# RS_485.net
KiCad netlist of a schematic drawn in Altium Designer
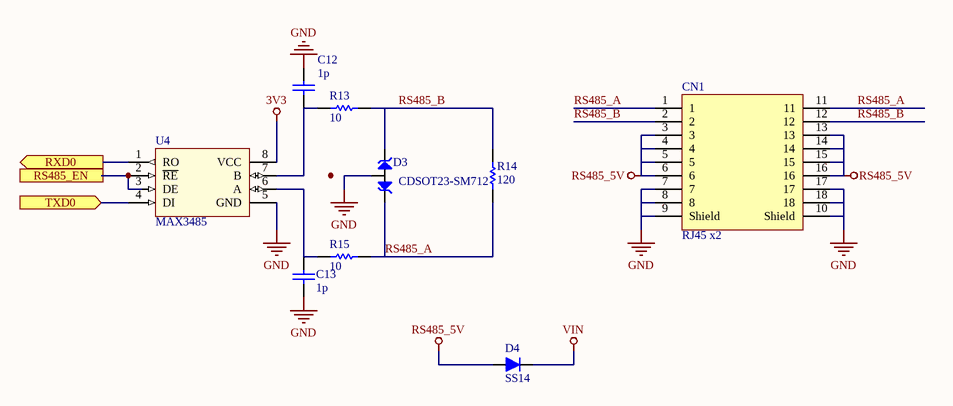
[diagram p0: RS_485.SchDoc]

(export (version "E")
  (design (tool "Eeschema 10.0.6"))
  (components
    (comp (ref "C12")
      (value "1p")
      (description "Capacitor")
      (libsource (lib "Simulation Generic Components") (part "Capacitor"))
    )
    (comp (ref "C13")
      (value "1p")
      (description "Capacitor")
      (libsource (lib "Simulation Generic Components") (part "Capacitor"))
    )
    (comp (ref "CN1")
      (value "RJ45 x2")
      (footprint "CONN/RJ45/x2")
      (description "Connector RJ45 X2")
      (libsource (lib "chipfc_altium_libs") (part "CON RJ45 x2"))
    )
    (comp (ref "D3")
      (value "CDSOT23-SM712")
      (footprint "SOT-23")
      (description "TVS DIODE 7V/12V 14V/26V SOT23-3")
      (libsource (lib "chipfc_altium_libs") (part "CDSOT23-SM712"))
    )
    (comp (ref "D4")
      (value "SS14")
      (footprint "DO-35 (SOD27 )")
      (description "Default Diode")
      (libsource (lib "chipfc_altium_libs") (part "Diode"))
    )
    (comp (ref "R13")
      (value "10")
      (description "Resistor")
      (libsource (lib "Simulation Generic Components") (part "Resistor"))
    )
    (comp (ref "R14")
      (value "120")
      (description "Resistor")
      (libsource (lib "Simulation Generic Components") (part "Resistor"))
    )
    (comp (ref "R15")
      (value "10")
      (description "Resistor")
      (libsource (lib "Simulation Generic Components") (part "Resistor"))
    )
    (comp (ref "U4")
      (value "MAX3485")
      (footprint "SOIC-8")
      (description "Low-Power, Slew-Rate-Limited  RS-485/RS-422 Transceivers")
      (libsource (lib "chipfc_altium_libs") (part "MAX485"))
    )
  )
  (nets
    (net (code "2") (name "/RS485_A") (class "Default")
      (node (ref "CN1") (pin "1") (pinfunction "1_1") (pintype "passive"))
      (node (ref "CN1") (pin "11") (pinfunction "11_11") (pintype "passive"))
      (node (ref "D3") (pin "1") (pinfunction "IO1_1") (pintype "passive"))
      (node (ref "R14") (pin "1") (pinfunction "1_1") (pintype "passive"))
      (node (ref "R15") (pin "2") (pinfunction "2_2") (pintype "passive"))
    )
    (net (code "3") (name "/RS485_B") (class "Default")
      (node (ref "CN1") (pin "12") (pinfunction "12_12") (pintype "passive"))
      (node (ref "CN1") (pin "2") (pinfunction "2_2") (pintype "passive"))
      (node (ref "D3") (pin "2") (pinfunction "IO2_2") (pintype "passive"))
      (node (ref "R13") (pin "2") (pinfunction "2_2") (pintype "passive"))
      (node (ref "R14") (pin "2") (pinfunction "2_2") (pintype "passive"))
    )
    (net (code "4") (name "/RS485_EN") (class "Default")
      (node (ref "U4") (pin "2") (pinfunction "~{RE}_2") (pintype "input"))
      (node (ref "U4") (pin "3") (pinfunction "DE_3") (pintype "input"))
    )
    (net (code "5") (name "/RXD0") (class "Default")
      (node (ref "U4") (pin "1") (pinfunction "RO_1") (pintype "output"))
    )
    (net (code "6") (name "/TXD0") (class "Default")
      (node (ref "U4") (pin "4") (pinfunction "DI_4") (pintype "input"))
    )
    (net (code "7") (name "3V3") (class "Default")
      (node (ref "U4") (pin "8") (pinfunction "VCC_8") (pintype "passive"))
    )
    (net (code "8") (name "GND") (class "Default")
      (node (ref "C12") (pin "2") (pinfunction "2_2") (pintype "passive"))
      (node (ref "C13") (pin "1") (pinfunction "1_1") (pintype "passive"))
      (node (ref "CN1") (pin "10") (pinfunction "Shield_10") (pintype "passive"))
      (node (ref "CN1") (pin "17") (pinfunction "17_17") (pintype "passive"))
      (node (ref "CN1") (pin "18") (pinfunction "18_18") (pintype "passive"))
      (node (ref "CN1") (pin "7") (pinfunction "7_7") (pintype "passive"))
      (node (ref "CN1") (pin "8") (pinfunction "8_8") (pintype "passive"))
      (node (ref "CN1") (pin "9") (pinfunction "Shield_9") (pintype "passive"))
      (node (ref "D3") (pin "3") (pinfunction "COM_3") (pintype "passive"))
      (node (ref "U4") (pin "5") (pinfunction "GND_5") (pintype "passive"))
    )
    (net (code "9") (name "Net-(U4-A)") (class "Default")
      (node (ref "C13") (pin "2") (pinfunction "2_2") (pintype "passive"))
      (node (ref "R15") (pin "1") (pinfunction "1_1") (pintype "passive"))
      (node (ref "U4") (pin "6") (pinfunction "A_6") (pintype "bidirectional"))
    )
    (net (code "10") (name "Net-(U4-B)") (class "Default")
      (node (ref "C12") (pin "1") (pinfunction "1_1") (pintype "passive"))
      (node (ref "R13") (pin "1") (pinfunction "1_1") (pintype "passive"))
      (node (ref "U4") (pin "7") (pinfunction "B_7") (pintype "bidirectional"))
    )
    (net (code "11") (name "RS485_5V") (class "Default")
      (node (ref "CN1") (pin "13") (pinfunction "13_13") (pintype "passive"))
      (node (ref "CN1") (pin "14") (pinfunction "14_14") (pintype "passive"))
      (node (ref "CN1") (pin "15") (pinfunction "15_15") (pintype "passive"))
      (node (ref "CN1") (pin "16") (pinfunction "16_16") (pintype "passive"))
      (node (ref "CN1") (pin "3") (pinfunction "3_3") (pintype "passive"))
      (node (ref "CN1") (pin "4") (pinfunction "4_4") (pintype "passive"))
      (node (ref "CN1") (pin "5") (pinfunction "5_5") (pintype "passive"))
      (node (ref "CN1") (pin "6") (pinfunction "6_6") (pintype "passive"))
      (node (ref "D4") (pin "1") (pinfunction "A_1") (pintype "passive"))
    )
    (net (code "12") (name "VIN") (class "Default")
      (node (ref "D4") (pin "2") (pinfunction "K_2") (pintype "passive"))
    )
  )
)
